# pierwszy_schemat_dobrow.net
KiCad netlist of a schematic drawn in EAGLE
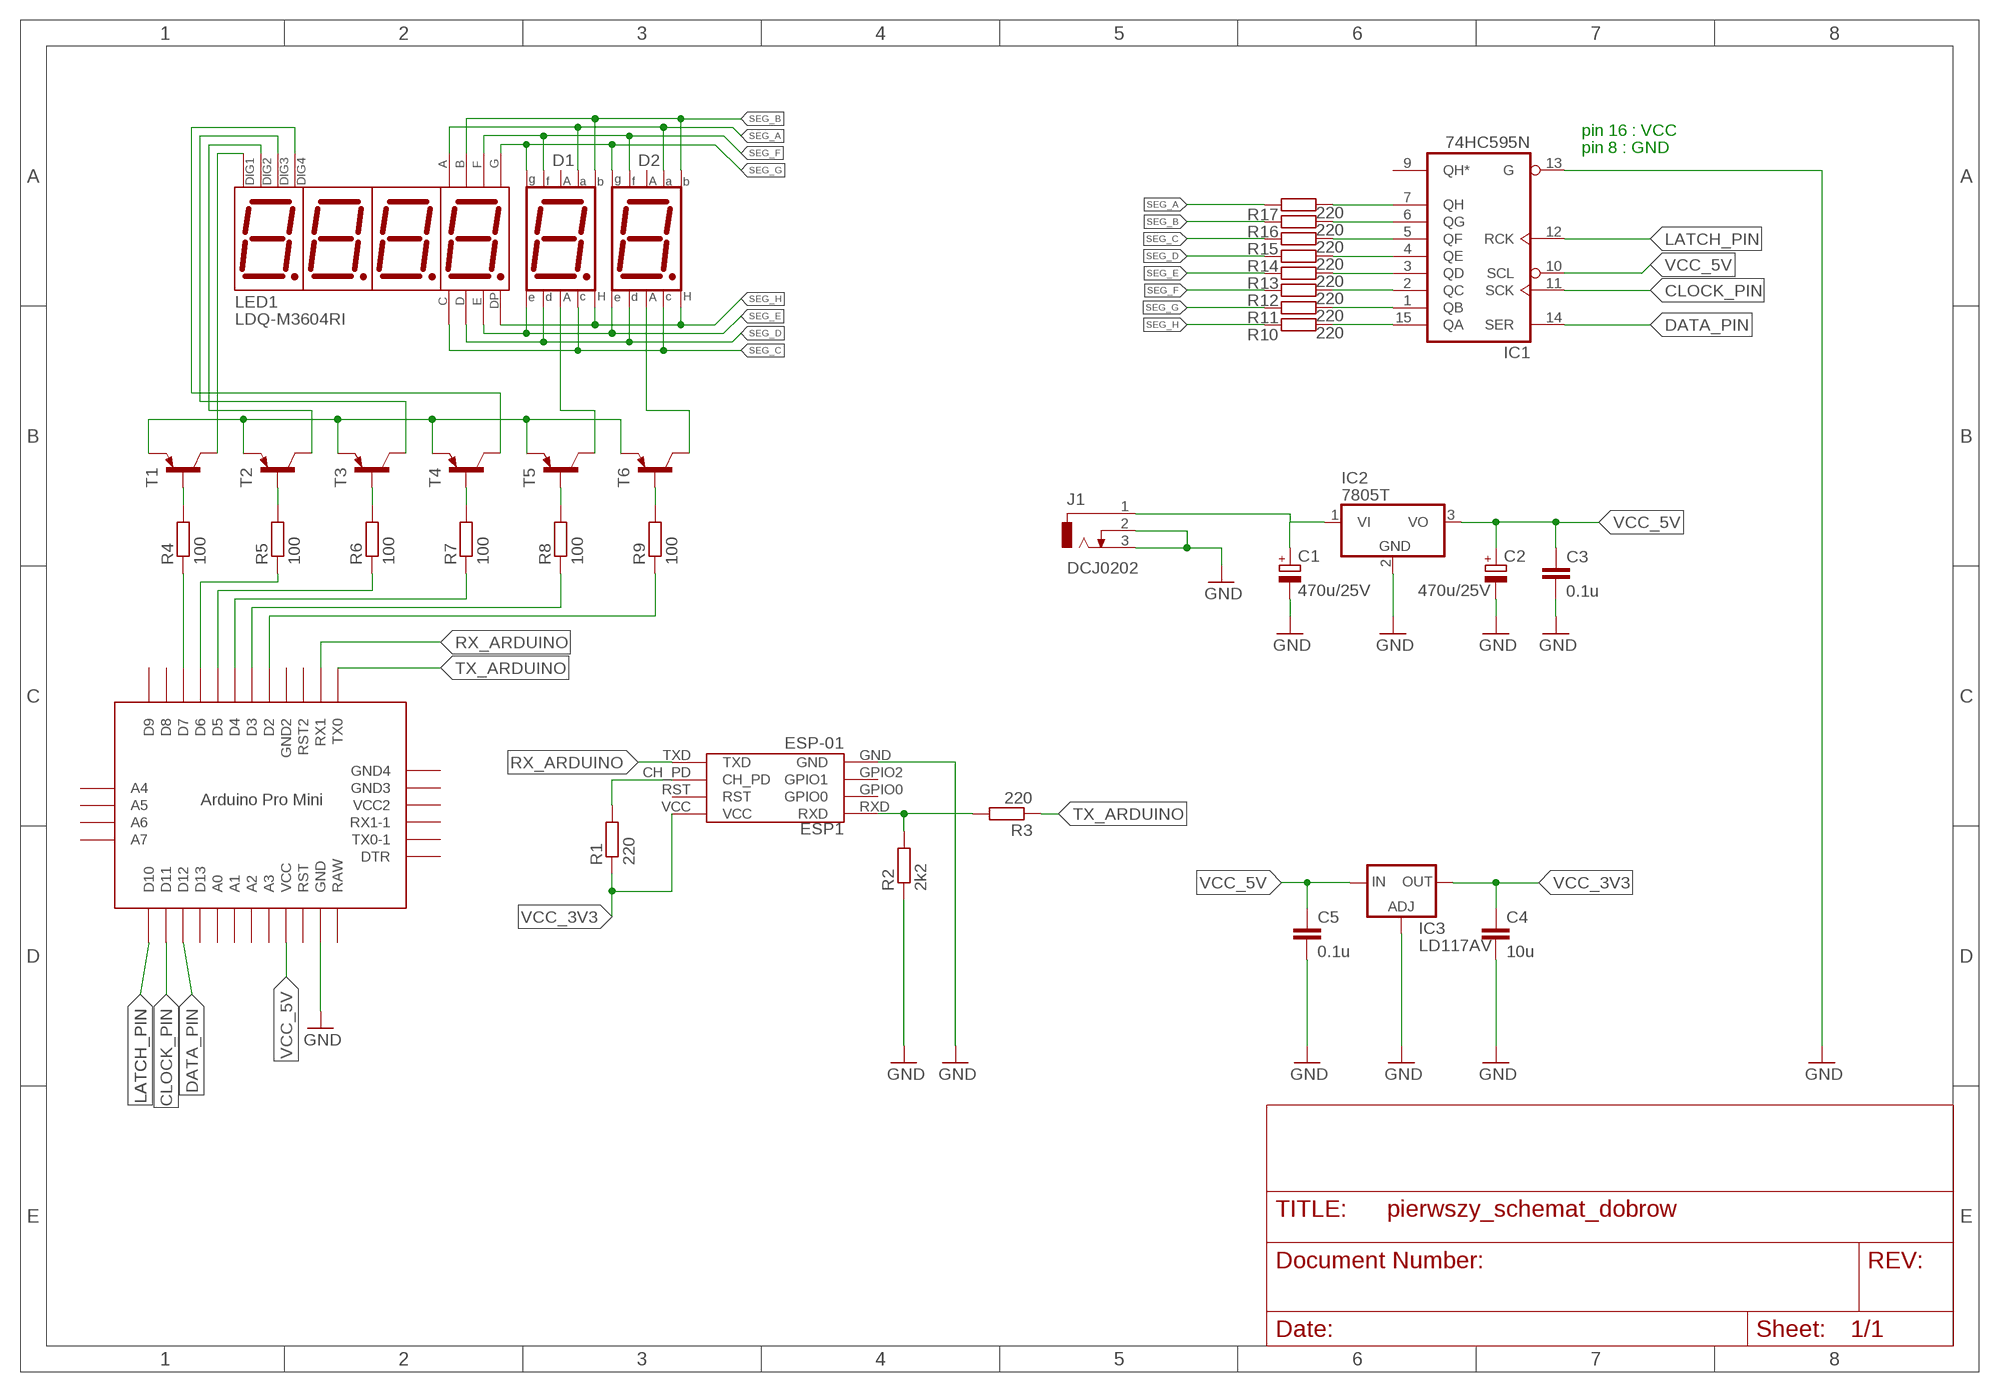
[diagram p0: schematic, sheet 1]

(export (version "E")
  (design (tool "Eeschema 10.0.6"))
  (components
    (comp (ref "C1")
      (value "470u/25V")
      (footprint "eagle-import:E5-8,5")
      (libsource (lib "eagle-import") (part "CPOL-EUE5-8.5"))
    )
    (comp (ref "C2")
      (value "470u/25V")
      (footprint "eagle-import:E5-8,5")
      (libsource (lib "eagle-import") (part "CPOL-EUE5-8.5"))
    )
    (comp (ref "C3")
      (value "0.1u")
      (footprint "eagle-import:C025-025X050")
      (libsource (lib "eagle-import") (part "C-EU025-025X050"))
    )
    (comp (ref "C4")
      (value "10u")
      (footprint "eagle-import:C025-025X050")
      (libsource (lib "eagle-import") (part "C-EU025-025X050"))
    )
    (comp (ref "C5")
      (value "0.1u")
      (footprint "eagle-import:C025-025X050")
      (libsource (lib "eagle-import") (part "C-EU025-025X050"))
    )
    (comp (ref "D1")
      (value "7SEG-CA")
      (footprint "eagle-import:7SEG-13")
      (libsource (lib "eagle-import") (part "7SEG-CA"))
    )
    (comp (ref "D2")
      (value "7SEG-CA")
      (footprint "eagle-import:7SEG-13")
      (libsource (lib "eagle-import") (part "7SEG-CA"))
    )
    (comp (ref "ESP1")
      (value "ESP-01")
      (footprint "eagle-import:ESP-01")
      (fields (field (name "MF") "AI-Thinker"))
      (libsource (lib "eagle-import") (part "ESP-01"))
    )
    (comp (ref "IC1")
      (value "74HC595N")
      (footprint "eagle-import:DIL16")
      (libsource (lib "eagle-import") (part "74595NHC"))
    )
    (comp (ref "IC2")
      (value "7805T")
      (footprint "eagle-import:TO220H")
      (libsource (lib "eagle-import") (part "78T05"))
    )
    (comp (ref "IC3")
      (value "LD117AV")
      (footprint "eagle-import:TO220L1")
      (libsource (lib "eagle-import") (part "LD117A?V"))
    )
    (comp (ref "J1")
      (value "DCJ0202")
      (footprint "eagle-import:DCJ0202")
      (libsource (lib "eagle-import") (part "DCJ0202"))
    )
    (comp (ref "LED1")
      (value "LDQ-M3604RI")
      (footprint "eagle-import:LDQ-M3604RI")
      (fields (field (name "MF") "Lumex"))
      (libsource (lib "eagle-import") (part "LDQ-M3604RI"))
    )
    (comp (ref "R1")
      (value "220")
      (footprint "eagle-import:0414_15")
      (libsource (lib "eagle-import") (part "R-EU_0414/15"))
    )
    (comp (ref "R2")
      (value "2k2")
      (footprint "eagle-import:0414_15")
      (libsource (lib "eagle-import") (part "R-EU_0414/15"))
    )
    (comp (ref "R3")
      (value "220")
      (footprint "eagle-import:0414_15")
      (libsource (lib "eagle-import") (part "R-EU_0414/15"))
    )
    (comp (ref "R4")
      (value "100")
      (footprint "eagle-import:0414_15")
      (libsource (lib "eagle-import") (part "R-EU_0414/15"))
    )
    (comp (ref "R5")
      (value "100")
      (footprint "eagle-import:0414_15")
      (libsource (lib "eagle-import") (part "R-EU_0414/15"))
    )
    (comp (ref "R6")
      (value "100")
      (footprint "eagle-import:0414_15")
      (libsource (lib "eagle-import") (part "R-EU_0414/15"))
    )
    (comp (ref "R7")
      (value "100")
      (footprint "eagle-import:0414_15")
      (libsource (lib "eagle-import") (part "R-EU_0414/15"))
    )
    (comp (ref "R8")
      (value "100")
      (footprint "eagle-import:0414_15")
      (libsource (lib "eagle-import") (part "R-EU_0414/15"))
    )
    (comp (ref "R9")
      (value "100")
      (footprint "eagle-import:0414_15")
      (libsource (lib "eagle-import") (part "R-EU_0414/15"))
    )
    (comp (ref "R10")
      (value "220")
      (footprint "eagle-import:0414_15")
      (libsource (lib "eagle-import") (part "R-EU_0414/15"))
    )
    (comp (ref "R11")
      (value "220")
      (footprint "eagle-import:0414_15")
      (libsource (lib "eagle-import") (part "R-EU_0414/15"))
    )
    (comp (ref "R12")
      (value "220")
      (footprint "eagle-import:0414_15")
      (libsource (lib "eagle-import") (part "R-EU_0414/15"))
    )
    (comp (ref "R13")
      (value "220")
      (footprint "eagle-import:0414_15")
      (libsource (lib "eagle-import") (part "R-EU_0414/15"))
    )
    (comp (ref "R14")
      (value "220")
      (footprint "eagle-import:0414_15")
      (libsource (lib "eagle-import") (part "R-EU_0414/15"))
    )
    (comp (ref "R15")
      (value "220")
      (footprint "eagle-import:0414_15")
      (libsource (lib "eagle-import") (part "R-EU_0414/15"))
    )
    (comp (ref "R16")
      (value "220")
      (footprint "eagle-import:0414_15")
      (libsource (lib "eagle-import") (part "R-EU_0414/15"))
    )
    (comp (ref "R17")
      (value "220")
      (footprint "eagle-import:0414_15")
      (libsource (lib "eagle-import") (part "R-EU_0414/15"))
    )
    (comp (ref "T1")
      (value "BC556A-PNP-TO92-EBC")
      (footprint "eagle-import:TO92-EBC")
      (libsource (lib "eagle-import") (part "-PNP-TO92-EBCBC556A"))
    )
    (comp (ref "T2")
      (value "BC556A-PNP-TO92-EBC")
      (footprint "eagle-import:TO92-EBC")
      (libsource (lib "eagle-import") (part "-PNP-TO92-EBCBC556A"))
    )
    (comp (ref "T3")
      (value "BC556A-PNP-TO92-EBC")
      (footprint "eagle-import:TO92-EBC")
      (libsource (lib "eagle-import") (part "-PNP-TO92-EBCBC556A"))
    )
    (comp (ref "T4")
      (value "BC556A-PNP-TO92-EBC")
      (footprint "eagle-import:TO92-EBC")
      (libsource (lib "eagle-import") (part "-PNP-TO92-EBCBC556A"))
    )
    (comp (ref "T5")
      (value "BC556A-PNP-TO92-EBC")
      (footprint "eagle-import:TO92-EBC")
      (libsource (lib "eagle-import") (part "-PNP-TO92-EBCBC556A"))
    )
    (comp (ref "T6")
      (value "BC556A-PNP-TO92-EBC")
      (footprint "eagle-import:TO92-EBC")
      (libsource (lib "eagle-import") (part "-PNP-TO92-EBCBC556A"))
    )
    (comp (ref "U$1")
      (value "PRO-MINI")
      (footprint "eagle-import:PRO-MINI")
      (libsource (lib "eagle-import") (part "PRO-MINI"))
    )
  )
  (nets
    (net (code "1") (name "/RAW") (class "Default")
      (node (ref "U$1") (pin "RAW") (pinfunction "RAW_RAW") (pintype "power_in"))
    )
    (net (code "2") (name "CLOCK_PIN") (class "Default")
      (node (ref "IC1") (pin "11") (pinfunction "SCK_11") (pintype "input"))
      (node (ref "U$1") (pin "D11") (pinfunction "D11_D11") (pintype "bidirectional"))
    )
    (net (code "3") (name "DATA_PIN") (class "Default")
      (node (ref "IC1") (pin "14") (pinfunction "SER_14") (pintype "input"))
      (node (ref "U$1") (pin "D12") (pinfunction "D12_D12") (pintype "bidirectional"))
    )
    (net (code "4") (name "GND") (class "Default")
      (node (ref "C1") (pin "-") (pinfunction "-_-") (pintype "passive"))
      (node (ref "C2") (pin "-") (pinfunction "-_-") (pintype "passive"))
      (node (ref "C3") (pin "2") (pinfunction "2_2") (pintype "passive"))
      (node (ref "C4") (pin "2") (pinfunction "2_2") (pintype "passive"))
      (node (ref "C5") (pin "2") (pinfunction "2_2") (pintype "passive"))
      (node (ref "ESP1") (pin "GND") (pinfunction "GND_GND") (pintype "bidirectional"))
      (node (ref "IC1") (pin "13") (pinfunction "G_13") (pintype "input"))
      (node (ref "IC2") (pin "2") (pinfunction "GND_2") (pintype "passive"))
      (node (ref "IC3") (pin "1") (pinfunction "ADJ_1") (pintype "input"))
      (node (ref "J1") (pin "2") (pinfunction "2_2") (pintype "passive"))
      (node (ref "J1") (pin "3") (pinfunction "3_3") (pintype "passive"))
      (node (ref "R2") (pin "1") (pinfunction "1_1") (pintype "passive"))
      (node (ref "U$1") (pin "GND") (pinfunction "GND_GND") (pintype "input"))
    )
    (net (code "5") (name "LATCH_PIN") (class "Default")
      (node (ref "IC1") (pin "12") (pinfunction "RCK_12") (pintype "input"))
      (node (ref "U$1") (pin "D10") (pinfunction "D10_D10") (pintype "bidirectional"))
    )
    (net (code "6") (name "Net-(D1-CA2)") (class "Default")
      (node (ref "D1") (pin "8") (pinfunction "CA2_8") (pintype "passive"))
      (node (ref "T5") (pin "C") (pinfunction "C_C") (pintype "passive"))
    )
    (net (code "7") (name "Net-(D2-CA2)") (class "Default")
      (node (ref "D2") (pin "8") (pinfunction "CA2_8") (pintype "passive"))
      (node (ref "T6") (pin "C") (pinfunction "C_C") (pintype "passive"))
    )
    (net (code "8") (name "Net-(ESP1-PadCH_PD)") (class "Default")
      (node (ref "ESP1") (pin "CH_PD") (pinfunction "CH_PD_CH_PD") (pintype "bidirectional"))
      (node (ref "R1") (pin "2") (pinfunction "2_2") (pintype "passive"))
    )
    (net (code "9") (name "Net-(IC1A-QA)") (class "Default")
      (node (ref "IC1") (pin "15") (pinfunction "QA_15") (pintype "tri_state"))
      (node (ref "R10") (pin "2") (pinfunction "2_2") (pintype "passive"))
    )
    (net (code "10") (name "Net-(IC1A-QB)") (class "Default")
      (node (ref "IC1") (pin "1") (pinfunction "QB_1") (pintype "tri_state"))
      (node (ref "R11") (pin "2") (pinfunction "2_2") (pintype "passive"))
    )
    (net (code "11") (name "Net-(IC1A-QC)") (class "Default")
      (node (ref "IC1") (pin "2") (pinfunction "QC_2") (pintype "tri_state"))
      (node (ref "R12") (pin "2") (pinfunction "2_2") (pintype "passive"))
    )
    (net (code "12") (name "Net-(IC1A-QD)") (class "Default")
      (node (ref "IC1") (pin "3") (pinfunction "QD_3") (pintype "tri_state"))
      (node (ref "R13") (pin "2") (pinfunction "2_2") (pintype "passive"))
    )
    (net (code "13") (name "Net-(IC1A-QE)") (class "Default")
      (node (ref "IC1") (pin "4") (pinfunction "QE_4") (pintype "tri_state"))
      (node (ref "R14") (pin "2") (pinfunction "2_2") (pintype "passive"))
    )
    (net (code "14") (name "Net-(IC1A-QF)") (class "Default")
      (node (ref "IC1") (pin "5") (pinfunction "QF_5") (pintype "tri_state"))
      (node (ref "R15") (pin "2") (pinfunction "2_2") (pintype "passive"))
    )
    (net (code "15") (name "Net-(IC1A-QG)") (class "Default")
      (node (ref "IC1") (pin "6") (pinfunction "QG_6") (pintype "tri_state"))
      (node (ref "R16") (pin "2") (pinfunction "2_2") (pintype "passive"))
    )
    (net (code "16") (name "Net-(IC1A-QH)") (class "Default")
      (node (ref "IC1") (pin "7") (pinfunction "QH_7") (pintype "tri_state"))
      (node (ref "R17") (pin "2") (pinfunction "2_2") (pintype "passive"))
    )
    (net (code "17") (name "Net-(IC2-VI)") (class "Default")
      (node (ref "C1") (pin "+") (pinfunction "+_+") (pintype "passive"))
      (node (ref "IC2") (pin "1") (pinfunction "VI_1") (pintype "input"))
      (node (ref "J1") (pin "1") (pinfunction "1_1") (pintype "passive"))
    )
    (net (code "18") (name "Net-(LED1-DIG1)") (class "Default")
      (node (ref "LED1") (pin "12") (pinfunction "DIG1_12") (pintype "bidirectional"))
      (node (ref "T1") (pin "C") (pinfunction "C_C") (pintype "passive"))
    )
    (net (code "19") (name "Net-(LED1-DIG2)") (class "Default")
      (node (ref "LED1") (pin "9") (pinfunction "DIG2_9") (pintype "bidirectional"))
      (node (ref "T2") (pin "C") (pinfunction "C_C") (pintype "passive"))
    )
    (net (code "20") (name "Net-(LED1-DIG3)") (class "Default")
      (node (ref "LED1") (pin "8") (pinfunction "DIG3_8") (pintype "bidirectional"))
      (node (ref "T3") (pin "C") (pinfunction "C_C") (pintype "passive"))
    )
    (net (code "21") (name "Net-(LED1-DIG4)") (class "Default")
      (node (ref "LED1") (pin "6") (pinfunction "DIG4_6") (pintype "bidirectional"))
      (node (ref "T4") (pin "C") (pinfunction "C_C") (pintype "passive"))
    )
    (net (code "22") (name "Net-(R4-Pad1)") (class "Default")
      (node (ref "R4") (pin "1") (pinfunction "1_1") (pintype "passive"))
      (node (ref "U$1") (pin "D7") (pinfunction "D7_D7") (pintype "bidirectional"))
    )
    (net (code "23") (name "Net-(R4-Pad2)") (class "Default")
      (node (ref "R4") (pin "2") (pinfunction "2_2") (pintype "passive"))
      (node (ref "T1") (pin "B") (pinfunction "B_B") (pintype "passive"))
    )
    (net (code "24") (name "Net-(R5-Pad1)") (class "Default")
      (node (ref "R5") (pin "1") (pinfunction "1_1") (pintype "passive"))
      (node (ref "U$1") (pin "D6") (pinfunction "D6_D6") (pintype "bidirectional"))
    )
    (net (code "25") (name "Net-(R5-Pad2)") (class "Default")
      (node (ref "R5") (pin "2") (pinfunction "2_2") (pintype "passive"))
      (node (ref "T2") (pin "B") (pinfunction "B_B") (pintype "passive"))
    )
    (net (code "26") (name "Net-(R6-Pad1)") (class "Default")
      (node (ref "R6") (pin "1") (pinfunction "1_1") (pintype "passive"))
      (node (ref "U$1") (pin "D5") (pinfunction "D5_D5") (pintype "bidirectional"))
    )
    (net (code "27") (name "Net-(R6-Pad2)") (class "Default")
      (node (ref "R6") (pin "2") (pinfunction "2_2") (pintype "passive"))
      (node (ref "T3") (pin "B") (pinfunction "B_B") (pintype "passive"))
    )
    (net (code "28") (name "Net-(R7-Pad1)") (class "Default")
      (node (ref "R7") (pin "1") (pinfunction "1_1") (pintype "passive"))
      (node (ref "U$1") (pin "D4") (pinfunction "D4_D4") (pintype "bidirectional"))
    )
    (net (code "29") (name "Net-(R7-Pad2)") (class "Default")
      (node (ref "R7") (pin "2") (pinfunction "2_2") (pintype "passive"))
      (node (ref "T4") (pin "B") (pinfunction "B_B") (pintype "passive"))
    )
    (net (code "30") (name "Net-(R8-Pad1)") (class "Default")
      (node (ref "R8") (pin "1") (pinfunction "1_1") (pintype "passive"))
      (node (ref "U$1") (pin "D3") (pinfunction "D3_D3") (pintype "bidirectional"))
    )
    (net (code "31") (name "Net-(R8-Pad2)") (class "Default")
      (node (ref "R8") (pin "2") (pinfunction "2_2") (pintype "passive"))
      (node (ref "T5") (pin "B") (pinfunction "B_B") (pintype "passive"))
    )
    (net (code "32") (name "Net-(R9-Pad1)") (class "Default")
      (node (ref "R9") (pin "1") (pinfunction "1_1") (pintype "passive"))
      (node (ref "U$1") (pin "D2") (pinfunction "D2_D2") (pintype "bidirectional"))
    )
    (net (code "33") (name "Net-(R9-Pad2)") (class "Default")
      (node (ref "R9") (pin "2") (pinfunction "2_2") (pintype "passive"))
      (node (ref "T6") (pin "B") (pinfunction "B_B") (pintype "passive"))
    )
    (net (code "34") (name "Net-(T1-PadE)") (class "Default")
      (node (ref "T1") (pin "E") (pinfunction "E_E") (pintype "passive"))
      (node (ref "T2") (pin "E") (pinfunction "E_E") (pintype "passive"))
      (node (ref "T3") (pin "E") (pinfunction "E_E") (pintype "passive"))
      (node (ref "T4") (pin "E") (pinfunction "E_E") (pintype "passive"))
      (node (ref "T5") (pin "E") (pinfunction "E_E") (pintype "passive"))
      (node (ref "T6") (pin "E") (pinfunction "E_E") (pintype "passive"))
    )
    (net (code "35") (name "RX_ARDUINO") (class "Default")
      (node (ref "ESP1") (pin "TXD") (pinfunction "TXD_TXD") (pintype "bidirectional"))
      (node (ref "U$1") (pin "RX1") (pinfunction "RX1_RX1") (pintype "bidirectional"))
    )
    (net (code "36") (name "SEG_A") (class "Default")
      (node (ref "D1") (pin "7") (pinfunction "A_7") (pintype "passive"))
      (node (ref "D2") (pin "7") (pinfunction "A_7") (pintype "passive"))
      (node (ref "LED1") (pin "11") (pinfunction "A_11") (pintype "bidirectional"))
      (node (ref "R17") (pin "1") (pinfunction "1_1") (pintype "passive"))
    )
    (net (code "37") (name "SEG_B") (class "Default")
      (node (ref "D1") (pin "6") (pinfunction "B_6") (pintype "passive"))
      (node (ref "D2") (pin "6") (pinfunction "B_6") (pintype "passive"))
      (node (ref "LED1") (pin "7") (pinfunction "B_7") (pintype "bidirectional"))
      (node (ref "R16") (pin "1") (pinfunction "1_1") (pintype "passive"))
    )
    (net (code "38") (name "SEG_C") (class "Default")
      (node (ref "D1") (pin "4") (pinfunction "C_4") (pintype "passive"))
      (node (ref "D2") (pin "4") (pinfunction "C_4") (pintype "passive"))
      (node (ref "LED1") (pin "4") (pinfunction "C_4") (pintype "bidirectional"))
      (node (ref "R15") (pin "1") (pinfunction "1_1") (pintype "passive"))
    )
    (net (code "39") (name "SEG_D") (class "Default")
      (node (ref "D1") (pin "2") (pinfunction "D_2") (pintype "passive"))
      (node (ref "D2") (pin "2") (pinfunction "D_2") (pintype "passive"))
      (node (ref "LED1") (pin "2") (pinfunction "D_2") (pintype "bidirectional"))
      (node (ref "R14") (pin "1") (pinfunction "1_1") (pintype "passive"))
    )
    (net (code "40") (name "SEG_E") (class "Default")
      (node (ref "D1") (pin "1") (pinfunction "E_1") (pintype "passive"))
      (node (ref "D2") (pin "1") (pinfunction "E_1") (pintype "passive"))
      (node (ref "LED1") (pin "1") (pinfunction "E_1") (pintype "bidirectional"))
      (node (ref "R13") (pin "1") (pinfunction "1_1") (pintype "passive"))
    )
    (net (code "41") (name "SEG_F") (class "Default")
      (node (ref "D1") (pin "9") (pinfunction "F_9") (pintype "passive"))
      (node (ref "D2") (pin "9") (pinfunction "F_9") (pintype "passive"))
      (node (ref "LED1") (pin "10") (pinfunction "F_10") (pintype "bidirectional"))
      (node (ref "R12") (pin "1") (pinfunction "1_1") (pintype "passive"))
    )
    (net (code "42") (name "SEG_G") (class "Default")
      (node (ref "D1") (pin "10") (pinfunction "G_10") (pintype "passive"))
      (node (ref "D2") (pin "10") (pinfunction "G_10") (pintype "passive"))
      (node (ref "LED1") (pin "5") (pinfunction "G_5") (pintype "bidirectional"))
      (node (ref "R11") (pin "1") (pinfunction "1_1") (pintype "passive"))
    )
    (net (code "43") (name "SEG_H") (class "Default")
      (node (ref "D1") (pin "5") (pinfunction "DP_5") (pintype "passive"))
      (node (ref "D2") (pin "5") (pinfunction "DP_5") (pintype "passive"))
      (node (ref "LED1") (pin "3") (pinfunction "DP_3") (pintype "bidirectional"))
      (node (ref "R10") (pin "1") (pinfunction "1_1") (pintype "passive"))
    )
    (net (code "44") (name "TX_ARDUINO") (class "Default")
      (node (ref "ESP1") (pin "RXD") (pinfunction "RXD_RXD") (pintype "bidirectional"))
      (node (ref "R2") (pin "2") (pinfunction "2_2") (pintype "passive"))
      (node (ref "R3") (pin "1") (pinfunction "1_1") (pintype "passive"))
      (node (ref "R3") (pin "2") (pinfunction "2_2") (pintype "passive"))
      (node (ref "U$1") (pin "TX0") (pinfunction "TX0_TX0") (pintype "bidirectional"))
    )
    (net (code "45") (name "VCC_3V3") (class "Default")
      (node (ref "C4") (pin "1") (pinfunction "1_1") (pintype "passive"))
      (node (ref "ESP1") (pin "VCC") (pinfunction "VCC_VCC") (pintype "bidirectional"))
      (node (ref "IC3") (pin "2") (pinfunction "OUT_2") (pintype "passive"))
      (node (ref "R1") (pin "1") (pinfunction "1_1") (pintype "passive"))
    )
    (net (code "46") (name "VCC_5V") (class "Default")
      (node (ref "C2") (pin "+") (pinfunction "+_+") (pintype "passive"))
      (node (ref "C3") (pin "1") (pinfunction "1_1") (pintype "passive"))
      (node (ref "C5") (pin "1") (pinfunction "1_1") (pintype "passive"))
      (node (ref "IC1") (pin "10") (pinfunction "SCL_10") (pintype "input"))
      (node (ref "IC2") (pin "3") (pinfunction "VO_3") (pintype "passive"))
      (node (ref "IC3") (pin "3") (pinfunction "IN_3") (pintype "input"))
      (node (ref "U$1") (pin "VCC") (pinfunction "VCC_VCC") (pintype "bidirectional"))
    )
    (net (code "47") (name "unconnected-(D1-CA1-Pad3)") (class "Default")
      (node (ref "D1") (pin "3") (pinfunction "CA1_3") (pintype "passive"))
    )
    (net (code "48") (name "unconnected-(D2-CA1-Pad3)") (class "Default")
      (node (ref "D2") (pin "3") (pinfunction "CA1_3") (pintype "passive"))
    )
    (net (code "49") (name "unconnected-(ESP1-GPIO1-PadGPIO2)") (class "Default")
      (node (ref "ESP1") (pin "GPIO2") (pinfunction "GPIO1_GPIO2") (pintype "bidirectional"))
    )
    (net (code "50") (name "unconnected-(ESP1-PadGPIO0)") (class "Default")
      (node (ref "ESP1") (pin "GPIO0") (pinfunction "GPIO0_GPIO0") (pintype "bidirectional"))
    )
    (net (code "51") (name "unconnected-(ESP1-PadRST)") (class "Default")
      (node (ref "ESP1") (pin "RST") (pinfunction "RST_RST") (pintype "bidirectional"))
    )
    (net (code "52") (name "unconnected-(IC1A-QH*-Pad9)") (class "Default")
      (node (ref "IC1") (pin "9") (pinfunction "QH*_9") (pintype "tri_state"))
    )
    (net (code "53") (name "unconnected-(U$1-GND2-PadGND1)") (class "Default")
      (node (ref "U$1") (pin "GND1") (pinfunction "GND2_GND1") (pintype "bidirectional"))
    )
    (net (code "54") (name "unconnected-(U$1-GND4-PadGND2)") (class "Default")
      (node (ref "U$1") (pin "GND2") (pinfunction "GND4_GND2") (pintype "bidirectional"))
    )
    (net (code "55") (name "unconnected-(U$1-PadA0)") (class "Default")
      (node (ref "U$1") (pin "A0") (pinfunction "A0_A0") (pintype "bidirectional"))
    )
    (net (code "56") (name "unconnected-(U$1-PadA1)") (class "Default")
      (node (ref "U$1") (pin "A1") (pinfunction "A1_A1") (pintype "bidirectional"))
    )
    (net (code "57") (name "unconnected-(U$1-PadA2)") (class "Default")
      (node (ref "U$1") (pin "A2") (pinfunction "A2_A2") (pintype "bidirectional"))
    )
    (net (code "58") (name "unconnected-(U$1-PadA3)") (class "Default")
      (node (ref "U$1") (pin "A3") (pinfunction "A3_A3") (pintype "bidirectional"))
    )
    (net (code "59") (name "unconnected-(U$1-PadA4)") (class "Default")
      (node (ref "U$1") (pin "A4") (pinfunction "A4_A4") (pintype "bidirectional"))
    )
    (net (code "60") (name "unconnected-(U$1-PadA5)") (class "Default")
      (node (ref "U$1") (pin "A5") (pinfunction "A5_A5") (pintype "bidirectional"))
    )
    (net (code "61") (name "unconnected-(U$1-PadA6)") (class "Default")
      (node (ref "U$1") (pin "A6") (pinfunction "A6_A6") (pintype "bidirectional"))
    )
    (net (code "62") (name "unconnected-(U$1-PadA7)") (class "Default")
      (node (ref "U$1") (pin "A7") (pinfunction "A7_A7") (pintype "bidirectional"))
    )
    (net (code "63") (name "unconnected-(U$1-PadD8)") (class "Default")
      (node (ref "U$1") (pin "D8") (pinfunction "D8_D8") (pintype "bidirectional"))
    )
    (net (code "64") (name "unconnected-(U$1-PadD9)") (class "Default")
      (node (ref "U$1") (pin "D9") (pinfunction "D9_D9") (pintype "bidirectional"))
    )
    (net (code "65") (name "unconnected-(U$1-PadD13)") (class "Default")
      (node (ref "U$1") (pin "D13") (pinfunction "D13_D13") (pintype "bidirectional"))
    )
    (net (code "66") (name "unconnected-(U$1-PadDTR)") (class "Default")
      (node (ref "U$1") (pin "DTR") (pinfunction "DTR_DTR") (pintype "bidirectional"))
    )
    (net (code "67") (name "unconnected-(U$1-PadGND3)") (class "Default")
      (node (ref "U$1") (pin "GND3") (pinfunction "GND3_GND3") (pintype "bidirectional"))
    )
    (net (code "68") (name "unconnected-(U$1-PadRST)") (class "Default")
      (node (ref "U$1") (pin "RST") (pinfunction "RST_RST") (pintype "bidirectional"))
    )
    (net (code "69") (name "unconnected-(U$1-PadRX1-1)") (class "Default")
      (node (ref "U$1") (pin "RX1-1") (pinfunction "RX1-1_RX1-1") (pintype "bidirectional"))
    )
    (net (code "70") (name "unconnected-(U$1-PadTX0-1)") (class "Default")
      (node (ref "U$1") (pin "TX0-1") (pinfunction "TX0-1_TX0-1") (pintype "bidirectional"))
    )
    (net (code "71") (name "unconnected-(U$1-RST2-PadRST1)") (class "Default")
      (node (ref "U$1") (pin "RST1") (pinfunction "RST2_RST1") (pintype "bidirectional"))
    )
    (net (code "72") (name "unconnected-(U$1-VCC2-PadVCC1)") (class "Default")
      (node (ref "U$1") (pin "VCC1") (pinfunction "VCC2_VCC1") (pintype "bidirectional"))
    )
  )
)
